# WFT0750CZ09_conv.net
KiCad netlist of a schematic drawn in EAGLE
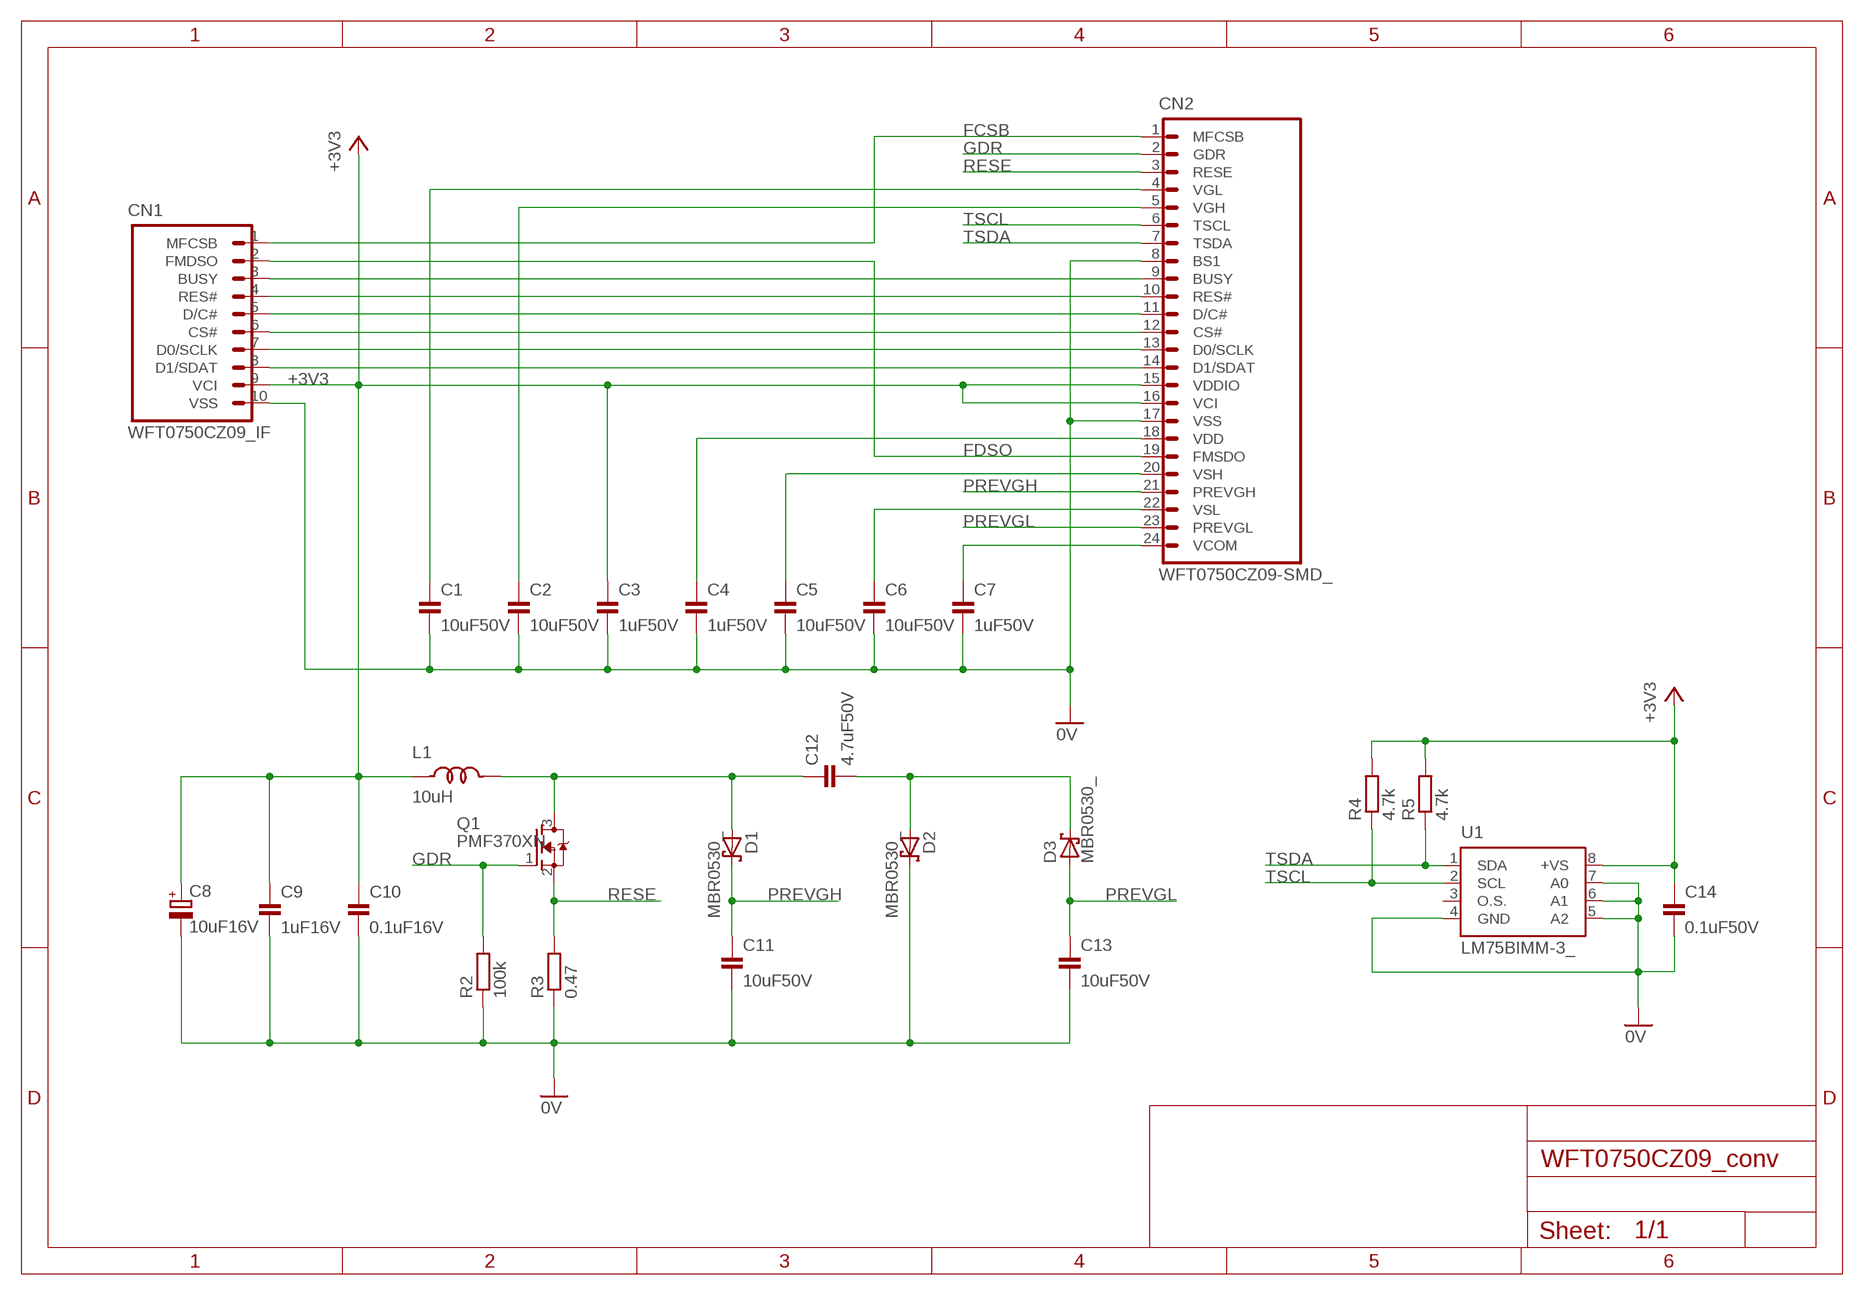
[diagram p0: schematic, sheet 1]

(export (version "E")
  (design (tool "Eeschema 10.0.6"))
  (components
    (comp (ref "C1")
      (value "10uF50V")
      (footprint "eagle-import:SMD_2012")
      (libsource (lib "eagle-import") (part "CAP_0805"))
    )
    (comp (ref "C2")
      (value "10uF50V")
      (footprint "eagle-import:SMD_2012")
      (libsource (lib "eagle-import") (part "CAP_0805"))
    )
    (comp (ref "C3")
      (value "1uF50V")
      (footprint "eagle-import:SMD_2012")
      (libsource (lib "eagle-import") (part "CAP_0805"))
    )
    (comp (ref "C4")
      (value "1uF50V")
      (footprint "eagle-import:SMD_2012")
      (libsource (lib "eagle-import") (part "CAP_0805"))
    )
    (comp (ref "C5")
      (value "10uF50V")
      (footprint "eagle-import:SMD_2012")
      (libsource (lib "eagle-import") (part "CAP_0805"))
    )
    (comp (ref "C6")
      (value "10uF50V")
      (footprint "eagle-import:SMD_2012")
      (libsource (lib "eagle-import") (part "CAP_0805"))
    )
    (comp (ref "C7")
      (value "1uF50V")
      (footprint "eagle-import:SMD_2012")
      (libsource (lib "eagle-import") (part "CAP_0805"))
    )
    (comp (ref "C8")
      (value "10uF16V")
      (footprint "eagle-import:C1210_TPST_DEV")
      (libsource (lib "eagle-import") (part "TPST106K016R0800_"))
    )
    (comp (ref "C9")
      (value "1uF16V")
      (footprint "eagle-import:SMD_2012")
      (libsource (lib "eagle-import") (part "CAP_0805"))
    )
    (comp (ref "C10")
      (value "0.1uF16V")
      (footprint "eagle-import:SMD_2012")
      (libsource (lib "eagle-import") (part "CAP_0805"))
    )
    (comp (ref "C11")
      (value "10uF50V")
      (footprint "eagle-import:SMD_2012")
      (libsource (lib "eagle-import") (part "CAP_0805"))
    )
    (comp (ref "C12")
      (value "4.7uF50V")
      (footprint "eagle-import:SMD_2012")
      (libsource (lib "eagle-import") (part "CAP_0805"))
    )
    (comp (ref "C13")
      (value "10uF50V")
      (footprint "eagle-import:SMD_2012")
      (libsource (lib "eagle-import") (part "CAP_0805"))
    )
    (comp (ref "C14")
      (value "0.1uF50V")
      (footprint "eagle-import:SMD_2012")
      (libsource (lib "eagle-import") (part "CAP_0805"))
    )
    (comp (ref "CN1")
      (value "WFT0750CZ09_IF")
      (footprint "eagle-import:WFT0750CZ09_IF_10PIN")
      (libsource (lib "eagle-import") (part "WFT0750CZ09_IF"))
    )
    (comp (ref "CN2")
      (value "WFT0750CZ09-SMD_")
      (footprint "eagle-import:FH12A-24S-0.5SH_DEV")
      (libsource (lib "eagle-import") (part "WFT0750CZ09-SMD_"))
    )
    (comp (ref "D1")
      (value "MBR0530_")
      (footprint "eagle-import:MBR0530_DEV")
      (libsource (lib "eagle-import") (part "MBR0530_"))
    )
    (comp (ref "D2")
      (value "MBR0530_")
      (footprint "eagle-import:MBR0530_DEV")
      (libsource (lib "eagle-import") (part "MBR0530_"))
    )
    (comp (ref "D3")
      (value "MBR0530_")
      (footprint "eagle-import:MBR0530_DEV")
      (libsource (lib "eagle-import") (part "MBR0530_"))
    )
    (comp (ref "L1")
      (value "10uH")
      (footprint "eagle-import:NLCV25T_DEV")
      (libsource (lib "eagle-import") (part "NLCV25T_"))
    )
    (comp (ref "Q1")
      (value "PMF370XN_")
      (footprint "eagle-import:SOT323_DEV")
      (libsource (lib "eagle-import") (part "PMF370XN_"))
    )
    (comp (ref "R2")
      (value "100k")
      (footprint "eagle-import:SMD_2012")
      (libsource (lib "eagle-import") (part "RESISTOR_0805"))
    )
    (comp (ref "R3")
      (value "0.47")
      (footprint "eagle-import:SMD_2012")
      (libsource (lib "eagle-import") (part "RESISTOR_0805"))
    )
    (comp (ref "R4")
      (value "4.7k")
      (footprint "eagle-import:SMD_2012")
      (libsource (lib "eagle-import") (part "RESISTOR_0805"))
    )
    (comp (ref "R5")
      (value "4.7k")
      (footprint "eagle-import:SMD_2012")
      (libsource (lib "eagle-import") (part "RESISTOR_0805"))
    )
    (comp (ref "U1")
      (value "LM75BIMM-3_")
      (footprint "eagle-import:SSOP8-DGK_DEV")
      (libsource (lib "eagle-import") (part "LM75BIMM-3_"))
    )
  )
  (nets
    (net (code "1") (name "+3V3") (class "Default")
      (node (ref "C10") (pin "1") (pinfunction "1_1") (pintype "passive"))
      (node (ref "C14") (pin "1") (pinfunction "1_1") (pintype "passive"))
      (node (ref "C3") (pin "1") (pinfunction "1_1") (pintype "passive"))
      (node (ref "C8") (pin "1") (pinfunction "+_1") (pintype "passive"))
      (node (ref "C9") (pin "1") (pinfunction "1_1") (pintype "passive"))
      (node (ref "CN1") (pin "9") (pinfunction "VCI_9") (pintype "passive"))
      (node (ref "CN2") (pin "15") (pinfunction "VDDIO_15") (pintype "passive"))
      (node (ref "CN2") (pin "16") (pinfunction "VCI_16") (pintype "passive"))
      (node (ref "L1") (pin "1") (pinfunction "1_1") (pintype "passive"))
      (node (ref "R4") (pin "2") (pinfunction "2_2") (pintype "passive"))
      (node (ref "R5") (pin "2") (pinfunction "2_2") (pintype "passive"))
      (node (ref "U1") (pin "8") (pinfunction "+VS_8") (pintype "passive"))
    )
    (net (code "2") (name "/FCSB") (class "Default")
      (node (ref "CN1") (pin "1") (pinfunction "MFCSB_1") (pintype "bidirectional"))
      (node (ref "CN2") (pin "1") (pinfunction "MFCSB_1") (pintype "input"))
    )
    (net (code "3") (name "/FDSO") (class "Default")
      (node (ref "CN1") (pin "2") (pinfunction "FMDSO_2") (pintype "bidirectional"))
      (node (ref "CN2") (pin "19") (pinfunction "FMSDO_19") (pintype "output"))
    )
    (net (code "4") (name "/GDR") (class "Default")
      (node (ref "CN2") (pin "2") (pinfunction "GDR_2") (pintype "output"))
      (node (ref "Q1") (pin "1") (pinfunction "G_1") (pintype "passive"))
      (node (ref "R2") (pin "2") (pinfunction "2_2") (pintype "passive"))
    )
    (net (code "5") (name "/PREVGH") (class "Default")
      (node (ref "C11") (pin "1") (pinfunction "1_1") (pintype "passive"))
      (node (ref "CN2") (pin "21") (pinfunction "PREVGH_21") (pintype "passive"))
      (node (ref "D1") (pin "1") (pinfunction "C_1") (pintype "passive"))
    )
    (net (code "6") (name "/PREVGL") (class "Default")
      (node (ref "C13") (pin "1") (pinfunction "1_1") (pintype "passive"))
      (node (ref "CN2") (pin "23") (pinfunction "PREVGL_23") (pintype "passive"))
      (node (ref "D3") (pin "2") (pinfunction "A_2") (pintype "passive"))
    )
    (net (code "7") (name "/RESE") (class "Default")
      (node (ref "CN2") (pin "3") (pinfunction "RESE_3") (pintype "output"))
      (node (ref "Q1") (pin "2") (pinfunction "S_2") (pintype "passive"))
      (node (ref "R3") (pin "2") (pinfunction "2_2") (pintype "passive"))
    )
    (net (code "8") (name "/TSCL") (class "Default")
      (node (ref "CN2") (pin "6") (pinfunction "TSCL_6") (pintype "output"))
      (node (ref "R4") (pin "1") (pinfunction "1_1") (pintype "passive"))
      (node (ref "U1") (pin "2") (pinfunction "SCL_2") (pintype "bidirectional"))
    )
    (net (code "9") (name "/TSDA") (class "Default")
      (node (ref "CN2") (pin "7") (pinfunction "TSDA_7") (pintype "bidirectional"))
      (node (ref "R5") (pin "1") (pinfunction "1_1") (pintype "passive"))
      (node (ref "U1") (pin "1") (pinfunction "SDA_1") (pintype "bidirectional"))
    )
    (net (code "10") (name "0V") (class "Default")
      (node (ref "C1") (pin "2") (pinfunction "2_2") (pintype "passive"))
      (node (ref "C10") (pin "2") (pinfunction "2_2") (pintype "passive"))
      (node (ref "C11") (pin "2") (pinfunction "2_2") (pintype "passive"))
      (node (ref "C13") (pin "2") (pinfunction "2_2") (pintype "passive"))
      (node (ref "C14") (pin "2") (pinfunction "2_2") (pintype "passive"))
      (node (ref "C2") (pin "2") (pinfunction "2_2") (pintype "passive"))
      (node (ref "C3") (pin "2") (pinfunction "2_2") (pintype "passive"))
      (node (ref "C4") (pin "2") (pinfunction "2_2") (pintype "passive"))
      (node (ref "C5") (pin "2") (pinfunction "2_2") (pintype "passive"))
      (node (ref "C6") (pin "2") (pinfunction "2_2") (pintype "passive"))
      (node (ref "C7") (pin "2") (pinfunction "2_2") (pintype "passive"))
      (node (ref "C8") (pin "2") (pinfunction "-_2") (pintype "passive"))
      (node (ref "C9") (pin "2") (pinfunction "2_2") (pintype "passive"))
      (node (ref "CN1") (pin "10") (pinfunction "VSS_10") (pintype "passive"))
      (node (ref "CN2") (pin "17") (pinfunction "VSS_17") (pintype "passive"))
      (node (ref "CN2") (pin "8") (pinfunction "BS1_8") (pintype "input"))
      (node (ref "D2") (pin "1") (pinfunction "C_1") (pintype "passive"))
      (node (ref "R2") (pin "1") (pinfunction "1_1") (pintype "passive"))
      (node (ref "R3") (pin "1") (pinfunction "1_1") (pintype "passive"))
      (node (ref "U1") (pin "4") (pinfunction "GND_4") (pintype "passive"))
      (node (ref "U1") (pin "5") (pinfunction "A2_5") (pintype "bidirectional"))
      (node (ref "U1") (pin "6") (pinfunction "A1_6") (pintype "bidirectional"))
      (node (ref "U1") (pin "7") (pinfunction "A0_7") (pintype "bidirectional"))
    )
    (net (code "11") (name "Net-(CN1-BUSY)") (class "Default")
      (node (ref "CN1") (pin "3") (pinfunction "BUSY_3") (pintype "bidirectional"))
      (node (ref "CN2") (pin "9") (pinfunction "BUSY_9") (pintype "output"))
    )
    (net (code "12") (name "Net-(CN1-CS#)") (class "Default")
      (node (ref "CN1") (pin "6") (pinfunction "CS#_6") (pintype "bidirectional"))
      (node (ref "CN2") (pin "12") (pinfunction "CS#_12") (pintype "input"))
    )
    (net (code "13") (name "Net-(CN1-D0{slash}SCLK)") (class "Default")
      (node (ref "CN1") (pin "7") (pinfunction "D0/SCLK_7") (pintype "bidirectional"))
      (node (ref "CN2") (pin "13") (pinfunction "D0/SCLK_13") (pintype "bidirectional"))
    )
    (net (code "14") (name "Net-(CN1-D1{slash}SDAT)") (class "Default")
      (node (ref "CN1") (pin "8") (pinfunction "D1/SDAT_8") (pintype "bidirectional"))
      (node (ref "CN2") (pin "14") (pinfunction "D1/SDAT_14") (pintype "bidirectional"))
    )
    (net (code "15") (name "Net-(CN1-D{slash}C#)") (class "Default")
      (node (ref "CN1") (pin "5") (pinfunction "D/C#_5") (pintype "bidirectional"))
      (node (ref "CN2") (pin "11") (pinfunction "D/C#_11") (pintype "input"))
    )
    (net (code "16") (name "Net-(CN1-RES#)") (class "Default")
      (node (ref "CN1") (pin "4") (pinfunction "RES#_4") (pintype "bidirectional"))
      (node (ref "CN2") (pin "10") (pinfunction "RES#_10") (pintype "input"))
    )
    (net (code "17") (name "Net-(CN2-VCOM)") (class "Default")
      (node (ref "C7") (pin "1") (pinfunction "1_1") (pintype "passive"))
      (node (ref "CN2") (pin "24") (pinfunction "VCOM_24") (pintype "passive"))
    )
    (net (code "18") (name "Net-(CN2-VDD)") (class "Default")
      (node (ref "C4") (pin "1") (pinfunction "1_1") (pintype "passive"))
      (node (ref "CN2") (pin "18") (pinfunction "VDD_18") (pintype "passive"))
    )
    (net (code "19") (name "Net-(CN2-VGH)") (class "Default")
      (node (ref "C2") (pin "1") (pinfunction "1_1") (pintype "passive"))
      (node (ref "CN2") (pin "5") (pinfunction "VGH_5") (pintype "passive"))
    )
    (net (code "20") (name "Net-(CN2-VGL)") (class "Default")
      (node (ref "C1") (pin "1") (pinfunction "1_1") (pintype "passive"))
      (node (ref "CN2") (pin "4") (pinfunction "VGL_4") (pintype "passive"))
    )
    (net (code "21") (name "Net-(CN2-VSH)") (class "Default")
      (node (ref "C5") (pin "1") (pinfunction "1_1") (pintype "passive"))
      (node (ref "CN2") (pin "20") (pinfunction "VSH_20") (pintype "passive"))
    )
    (net (code "22") (name "Net-(CN2-VSL)") (class "Default")
      (node (ref "C6") (pin "1") (pinfunction "1_1") (pintype "passive"))
      (node (ref "CN2") (pin "22") (pinfunction "VSL_22") (pintype "passive"))
    )
    (net (code "23") (name "Net-(D1-A)") (class "Default")
      (node (ref "C12") (pin "1") (pinfunction "1_1") (pintype "passive"))
      (node (ref "D1") (pin "2") (pinfunction "A_2") (pintype "passive"))
      (node (ref "L1") (pin "2") (pinfunction "2_2") (pintype "passive"))
      (node (ref "Q1") (pin "3") (pinfunction "D_3") (pintype "passive"))
    )
    (net (code "24") (name "Net-(D2-A)") (class "Default")
      (node (ref "C12") (pin "2") (pinfunction "2_2") (pintype "passive"))
      (node (ref "D2") (pin "2") (pinfunction "A_2") (pintype "passive"))
      (node (ref "D3") (pin "1") (pinfunction "C_1") (pintype "passive"))
    )
    (net (code "25") (name "unconnected-(U1-O.S.-Pad3)") (class "Default")
      (node (ref "U1") (pin "3") (pinfunction "O.S._3") (pintype "bidirectional"))
    )
  )
)
